# Power_Input_FET.net
KiCad netlist of a schematic drawn in Altium Designer
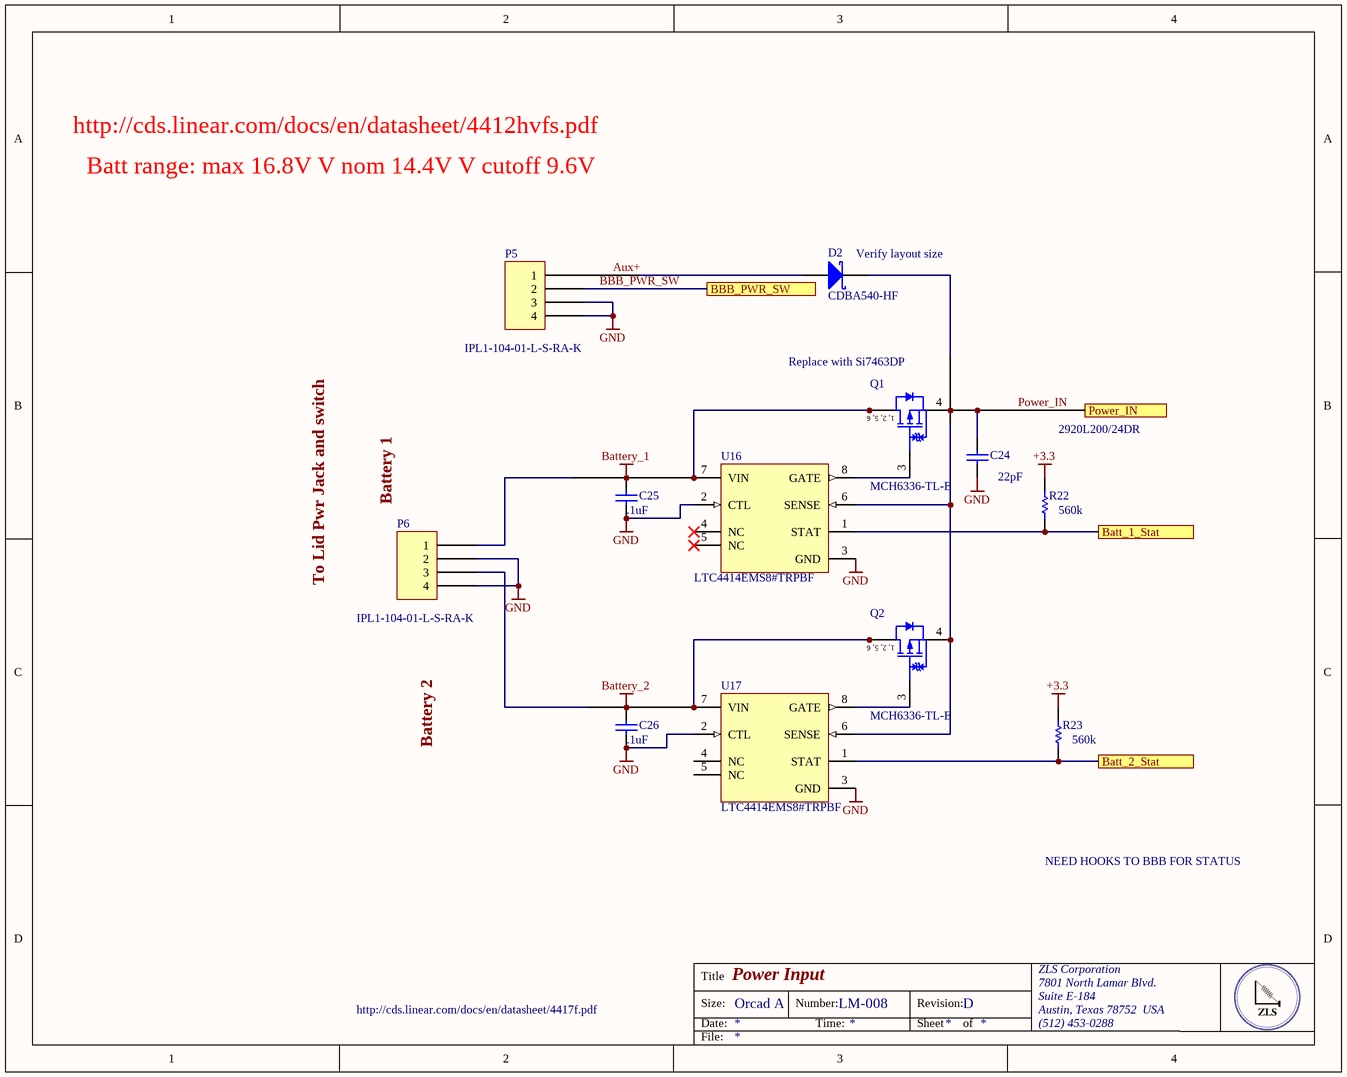
[diagram p0: Power_Input_FET.SchDoc]

(export (version "E")
  (design (tool "Eeschema 10.0.6"))
  (components
    (comp (ref "C24")
      (value "CAP CER 10UF 6.3V X5R 1206")
      (footprint "CAPC1206(3216)130_N")
      (fields
        (field (name "MANUFACTURER") "Taiyo Yuden")
        (field (name "MANUFACTURER PART NUMBER") "JMK316BJ106ML-T")
        (field (name "TOLERANCE") "±20%")
        (field (name "CAPACITANCE") "22pF")
      )
      (libsource (lib "Altium Content Vault") (part "CMP-1037-04913-1"))
    )
    (comp (ref "C25")
      (value "CAP CER 10UF 6.3V X5R 1206")
      (footprint "CAPC1206(3216)130_N")
      (fields
        (field (name "MANUFACTURER") "Taiyo Yuden")
        (field (name "MANUFACTURER PART NUMBER") "JMK316BJ106ML-T")
        (field (name "TOLERANCE") "±20%")
        (field (name "CAPACITANCE") ".1uF")
      )
      (libsource (lib "Altium Content Vault") (part "CMP-1037-04913-1"))
    )
    (comp (ref "C26")
      (value "CAP CER 10UF 6.3V X5R 1206")
      (footprint "CAPC1206(3216)130_N")
      (fields
        (field (name "MANUFACTURER") "Taiyo Yuden")
        (field (name "MANUFACTURER PART NUMBER") "JMK316BJ106ML-T")
        (field (name "TOLERANCE") "±20%")
        (field (name "CAPACITANCE") ".1uF")
      )
      (libsource (lib "Altium Content Vault") (part "CMP-1037-04913-1"))
    )
    (comp (ref "D2")
      (value "CDBA540-HF")
      (footprint "VISH-DO-214AC-2_M")
      (description "DIODE SCHOTTKY 40V 5A DO214AB")
      (fields (field (name "MANUFACTURER") "Comchip Technology"))
      (libsource (lib "Miscellaneous Devices") (part "D Schottky"))
    )
    (comp (ref "P5")
      (value "IPL1-104-01-L-S-RA-K")
      (footprint "IPL1-104-01-L-S-RA-K")
      (fields
        (field (name "MANUFACTURER") "Samtec Inc.")
        (field (name "MANUFACTURER PART NUMBER") "IPL1-104-01-L-S-RA-K")
      )
      (libsource (lib "ZLS_Schematic_lib") (part "IPL1-104-01-L-S-RA-K"))
    )
    (comp (ref "P6")
      (value "IPL1-104-01-L-S-RA-K")
      (footprint "IPL1-104-01-L-S-RA-K")
      (fields
        (field (name "MANUFACTURER") "Samtec Inc.")
        (field (name "MANUFACTURER PART NUMBER") "IPL1-104-01-L-S-RA-K")
      )
      (libsource (lib "ZLS_Schematic_lib") (part "IPL1-104-01-L-S-RA-K"))
    )
    (comp (ref "Q1")
      (value "MCH6336-TL-E")
      (footprint "ONSC-MCPH-6_V")
      (description "P-Channel Power MOSFET, -12 V, -5 A, 43 mOhm, Single, 6-Pin MCPH, Pb-Free, Tape and Reel")
      (fields (field (name "MANUFACTURER") "On Semiconductor"))
      (libsource (lib "Altium Content Vault") (part "ONSC-PMOS-6_B"))
    )
    (comp (ref "Q2")
      (value "MCH6336-TL-E")
      (footprint "ONSC-MCPH-6_V")
      (description "P-Channel Power MOSFET, -12 V, -5 A, 43 mOhm, Single, 6-Pin MCPH, Pb-Free, Tape and Reel")
      (fields (field (name "MANUFACTURER") "On Semiconductor"))
      (libsource (lib "Altium Content Vault") (part "ONSC-PMOS-6_B"))
    )
    (comp (ref "R22")
      (value "560k")
      (footprint "RESC0402(1005)_L")
      (fields (field (name "TOLERANCE") "±1%"))
      (libsource (lib "Altium Content Vault") (part "CMP-1011-00927-1"))
    )
    (comp (ref "R23")
      (value "560k")
      (footprint "RESC0402(1005)_L")
      (fields (field (name "TOLERANCE") "±1%"))
      (libsource (lib "Altium Content Vault") (part "CMP-1011-00927-1"))
    )
    (comp (ref "U16")
      (value "LTC4414EMS8#TRPBF")
      (footprint "LT-MS8-8_L")
      (fields (field (name "MANUFACTURER") "Linear Technology"))
      (libsource (lib "Altium Content Vault") (part "CMP-0479-00214-1"))
    )
    (comp (ref "U17")
      (value "LTC4414EMS8#TRPBF")
      (footprint "LT-MS8-8_L")
      (fields (field (name "MANUFACTURER") "Linear Technology"))
      (libsource (lib "Altium Content Vault") (part "CMP-0479-00214-1"))
    )
  )
  (nets
    (net (code "1") (name "+3.3") (class "Default")
      (node (ref "R22") (pin "2") (pinfunction "2_2") (pintype "passive"))
      (node (ref "R23") (pin "2") (pinfunction "2_2") (pintype "passive"))
    )
    (net (code "2") (name "/Aux+") (class "Default")
      (node (ref "D2") (pin "1") (pinfunction "A_1") (pintype "passive"))
      (node (ref "P5") (pin "1") (pinfunction "1_1") (pintype "passive"))
    )
    (net (code "3") (name "/BBB_PWR_SW") (class "Default")
      (node (ref "P5") (pin "2") (pinfunction "2_2") (pintype "passive"))
    )
    (net (code "4") (name "/Batt_1_Stat") (class "Default")
      (node (ref "R22") (pin "1") (pinfunction "1_1") (pintype "passive"))
      (node (ref "U16") (pin "1") (pinfunction "STAT_1") (pintype "open_collector"))
    )
    (net (code "5") (name "/Batt_2_Stat") (class "Default")
      (node (ref "R23") (pin "1") (pinfunction "1_1") (pintype "passive"))
      (node (ref "U17") (pin "1") (pinfunction "STAT_1") (pintype "open_collector"))
    )
    (net (code "6") (name "/Power_IN") (class "Default")
      (node (ref "C24") (pin "2") (pinfunction "2_2") (pintype "passive"))
      (node (ref "D2") (pin "2") (pinfunction "K_2") (pintype "passive"))
      (node (ref "Q1") (pin "4") (pinfunction "S_4") (pintype "passive"))
      (node (ref "Q2") (pin "4") (pinfunction "S_4") (pintype "passive"))
      (node (ref "U16") (pin "6") (pinfunction "SENSE_6") (pintype "input"))
      (node (ref "U17") (pin "6") (pinfunction "SENSE_6") (pintype "input"))
    )
    (net (code "7") (name "Battery_1") (class "Default")
      (node (ref "C25") (pin "2") (pinfunction "2_2") (pintype "passive"))
      (node (ref "P6") (pin "1") (pinfunction "1_1") (pintype "passive"))
      (node (ref "Q1") (pin "1") (pinfunction "D_1") (pintype "passive"))
      (node (ref "Q1") (pin "2") (pinfunction "D_2") (pintype "passive"))
      (node (ref "Q1") (pin "5") (pinfunction "D_5") (pintype "passive"))
      (node (ref "Q1") (pin "6") (pinfunction "D_6") (pintype "passive"))
      (node (ref "U16") (pin "7") (pinfunction "VIN_7") (pintype "power_in"))
    )
    (net (code "8") (name "Battery_2") (class "Default")
      (node (ref "C26") (pin "2") (pinfunction "2_2") (pintype "passive"))
      (node (ref "P6") (pin "3") (pinfunction "3_3") (pintype "passive"))
      (node (ref "Q2") (pin "1") (pinfunction "D_1") (pintype "passive"))
      (node (ref "Q2") (pin "2") (pinfunction "D_2") (pintype "passive"))
      (node (ref "Q2") (pin "5") (pinfunction "D_5") (pintype "passive"))
      (node (ref "Q2") (pin "6") (pinfunction "D_6") (pintype "passive"))
      (node (ref "U17") (pin "7") (pinfunction "VIN_7") (pintype "power_in"))
    )
    (net (code "9") (name "GND") (class "Default")
      (node (ref "C24") (pin "1") (pinfunction "1_1") (pintype "passive"))
      (node (ref "C25") (pin "1") (pinfunction "1_1") (pintype "passive"))
      (node (ref "C26") (pin "1") (pinfunction "1_1") (pintype "passive"))
      (node (ref "P5") (pin "3") (pinfunction "3_3") (pintype "passive"))
      (node (ref "P5") (pin "4") (pinfunction "4_4") (pintype "passive"))
      (node (ref "P6") (pin "2") (pinfunction "2_2") (pintype "passive"))
      (node (ref "P6") (pin "4") (pinfunction "4_4") (pintype "passive"))
      (node (ref "U16") (pin "2") (pinfunction "CTL_2") (pintype "input"))
      (node (ref "U16") (pin "3") (pinfunction "GND_3") (pintype "power_in"))
      (node (ref "U17") (pin "2") (pinfunction "CTL_2") (pintype "input"))
      (node (ref "U17") (pin "3") (pinfunction "GND_3") (pintype "power_in"))
    )
    (net (code "10") (name "Net-(Q1-G)") (class "Default")
      (node (ref "Q1") (pin "3") (pinfunction "G_3") (pintype "passive"))
      (node (ref "U16") (pin "8") (pinfunction "GATE_8") (pintype "output"))
    )
    (net (code "11") (name "Net-(Q2-G)") (class "Default")
      (node (ref "Q2") (pin "3") (pinfunction "G_3") (pintype "passive"))
      (node (ref "U17") (pin "8") (pinfunction "GATE_8") (pintype "output"))
    )
    (net (code "12") (name "unconnected-(U16-NC-Pad4)") (class "Default")
      (node (ref "U16") (pin "4") (pinfunction "NC_4") (pintype "passive+no_connect"))
    )
    (net (code "13") (name "unconnected-(U16-NC-Pad5)") (class "Default")
      (node (ref "U16") (pin "5") (pinfunction "NC_5") (pintype "passive+no_connect"))
    )
    (net (code "14") (name "unconnected-(U17-NC-Pad4)") (class "Default")
      (node (ref "U17") (pin "4") (pinfunction "NC_4") (pintype "passive"))
    )
    (net (code "15") (name "unconnected-(U17-NC-Pad5)") (class "Default")
      (node (ref "U17") (pin "5") (pinfunction "NC_5") (pintype "passive"))
    )
  )
)
